# LightPlay1.net
KiCad netlist of a schematic drawn in EAGLE
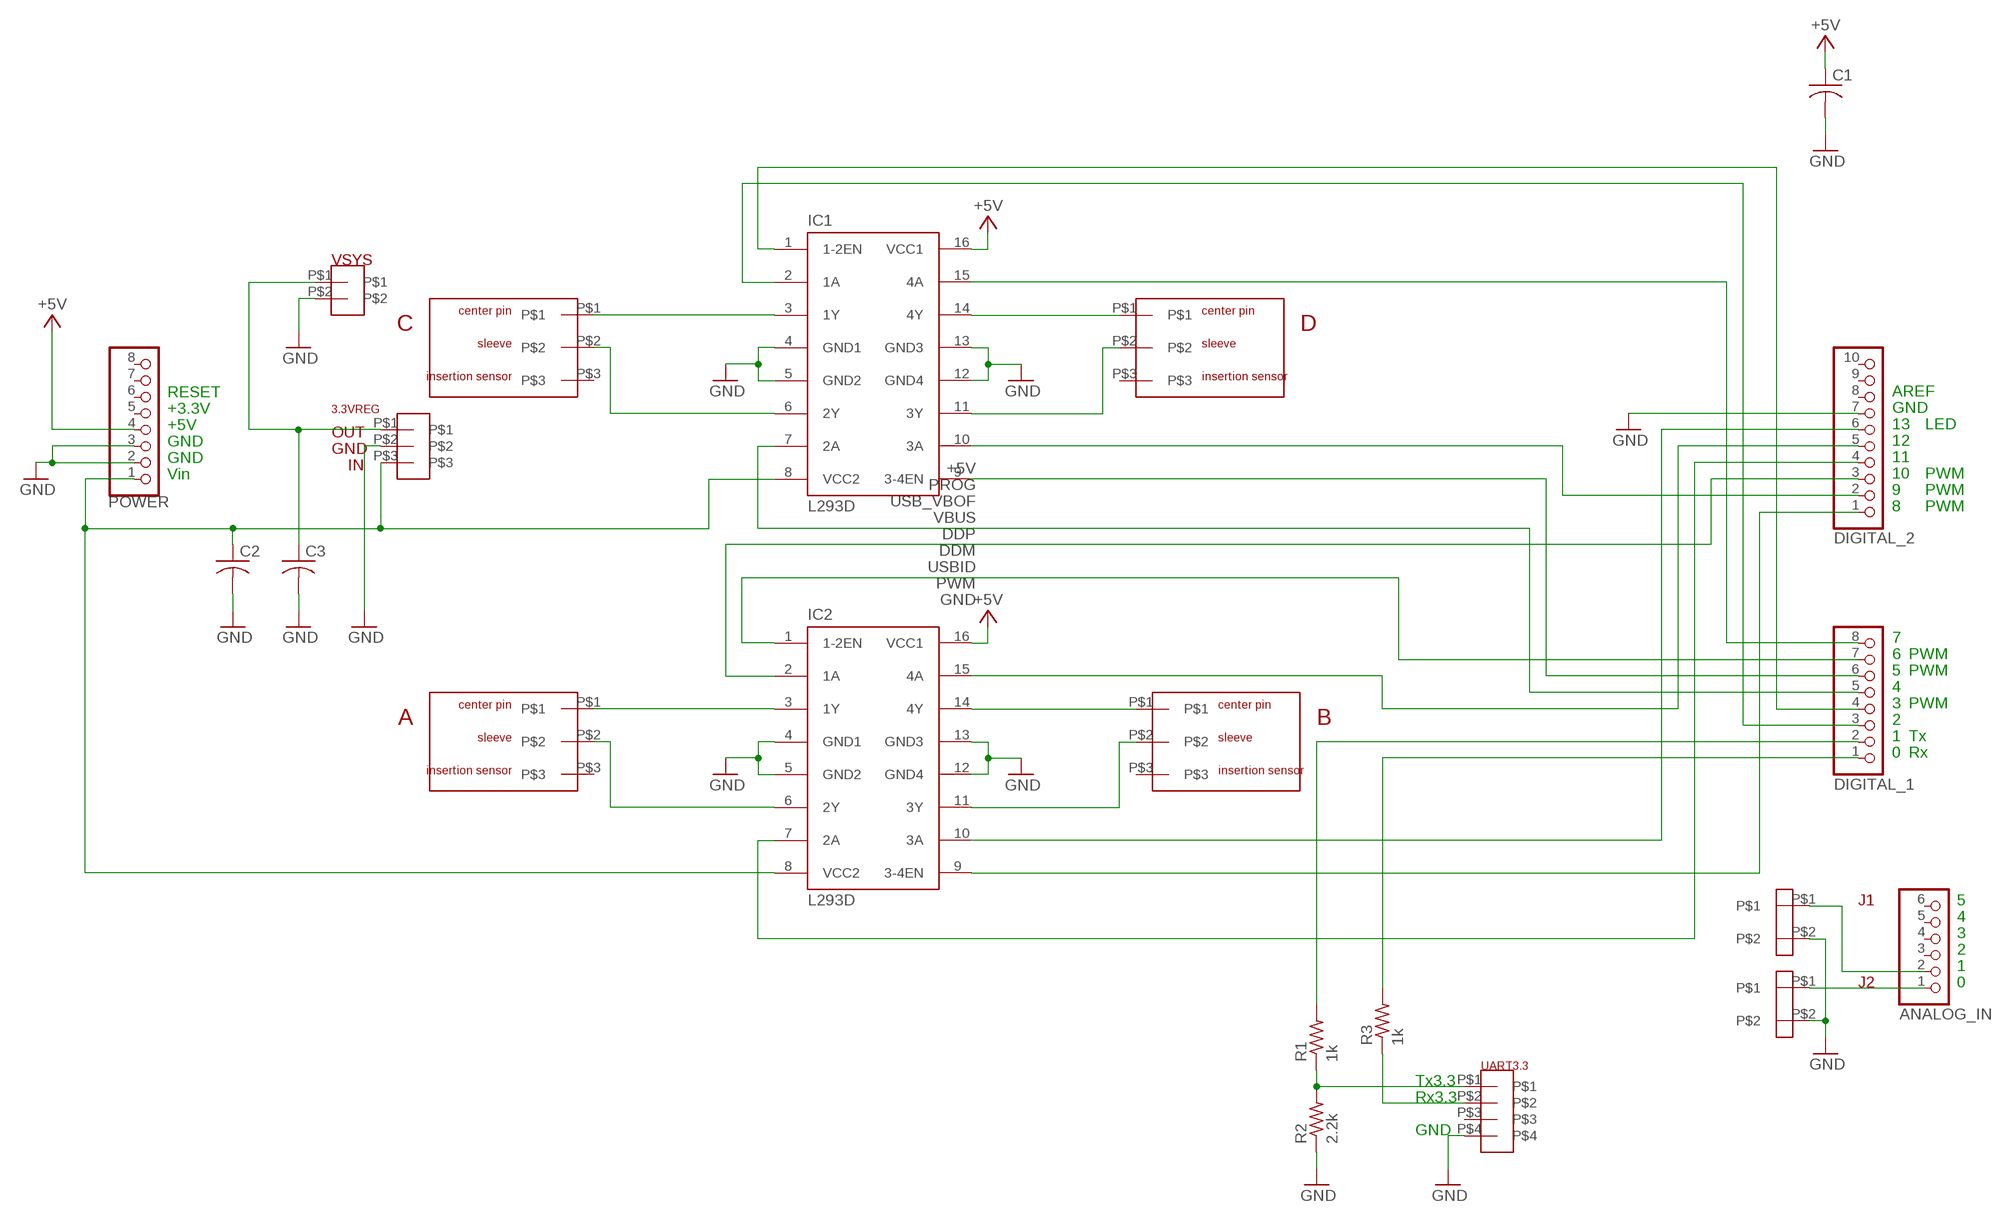
[diagram p0: schematic, sheet 1]

(export (version "E")
  (design (tool "Eeschema 10.0.6"))
  (components
    (comp (ref "3.3VREG")
      (value "LP38691_33REG")
      (footprint "eagle-import:TO-252")
      (libsource (lib "eagle-import") (part "LP38691_33REG"))
    )
    (comp (ref "A")
      (value "PJ-075DH-SMT-TR")
      (footprint "eagle-import:PJ-075DH-SMT-TR")
      (libsource (lib "eagle-import") (part "PJ-075DH-SMT-TR"))
    )
    (comp (ref "ANALOG_IN")
      (value "PINHD-1X6TH")
      (footprint "eagle-import:1X06-TH")
      (libsource (lib "eagle-import") (part "PINHD-1X6TH"))
    )
    (comp (ref "B")
      (value "PJ-075DH-SMT-TR")
      (footprint "eagle-import:PJ-075DH-SMT-TR")
      (libsource (lib "eagle-import") (part "PJ-075DH-SMT-TR"))
    )
    (comp (ref "C")
      (value "PJ-075DH-SMT-TR")
      (footprint "eagle-import:PJ-075DH-SMT-TR")
      (libsource (lib "eagle-import") (part "PJ-075DH-SMT-TR"))
    )
    (comp (ref "C1")
      (value "C-USC1206")
      (footprint "eagle-import:C1206")
      (libsource (lib "eagle-import") (part "C-USC1206"))
    )
    (comp (ref "C2")
      (value "C-USC1206")
      (footprint "eagle-import:C1206")
      (libsource (lib "eagle-import") (part "C-USC1206"))
    )
    (comp (ref "C3")
      (value "C-USC1206")
      (footprint "eagle-import:C1206")
      (libsource (lib "eagle-import") (part "C-USC1206"))
    )
    (comp (ref "D")
      (value "PJ-075DH-SMT-TR")
      (footprint "eagle-import:PJ-075DH-SMT-TR")
      (libsource (lib "eagle-import") (part "PJ-075DH-SMT-TR"))
    )
    (comp (ref "DIGITAL_1")
      (value "PINHD-1X8TH")
      (footprint "eagle-import:1X08-TH")
      (libsource (lib "eagle-import") (part "PINHD-1X8TH"))
    )
    (comp (ref "DIGITAL_2")
      (value "PINHD-1X10TH")
      (footprint "eagle-import:1X10-TH")
      (libsource (lib "eagle-import") (part "PINHD-1X10TH"))
    )
    (comp (ref "IC1")
      (value "L293D")
      (footprint "eagle-import:DIL16")
      (libsource (lib "eagle-import") (part "L293D"))
    )
    (comp (ref "IC2")
      (value "L293D")
      (footprint "eagle-import:DIL16")
      (libsource (lib "eagle-import") (part "L293D"))
    )
    (comp (ref "J1")
      (value "3.5MM_2PIN_SCREWTERMINAL_SPARKFUN")
      (footprint "eagle-import:1X02_3.5_SCREWTERM")
      (libsource (lib "eagle-import") (part "3.5MM_2PIN_SCREWTERMINAL_SPARKFUN"))
    )
    (comp (ref "J2")
      (value "3.5MM_2PIN_SCREWTERMINAL_SPARKFUN")
      (footprint "eagle-import:1X02_3.5_SCREWTERM")
      (libsource (lib "eagle-import") (part "3.5MM_2PIN_SCREWTERMINAL_SPARKFUN"))
    )
    (comp (ref "POWER")
      (value "PINHD-1X8TH")
      (footprint "eagle-import:1X08-TH")
      (libsource (lib "eagle-import") (part "PINHD-1X8TH"))
    )
    (comp (ref "R1")
      (value "1k")
      (footprint "eagle-import:M1206")
      (libsource (lib "eagle-import") (part "R-US_M1206"))
    )
    (comp (ref "R2")
      (value "2.2k")
      (footprint "eagle-import:M1206")
      (libsource (lib "eagle-import") (part "R-US_M1206"))
    )
    (comp (ref "R3")
      (value "1k")
      (footprint "eagle-import:M1206")
      (libsource (lib "eagle-import") (part "R-US_M1206"))
    )
    (comp (ref "UART3.3")
      (value "4PADS_ROBBIE")
      (footprint "eagle-import:1X04_ROBBIE")
      (libsource (lib "eagle-import") (part "4PADS_ROBBIE"))
    )
    (comp (ref "VSYS")
      (value "1X2HEADER_ROBBIE")
      (footprint "eagle-import:1X2HEADER_ROBBIE")
      (libsource (lib "eagle-import") (part "1X2HEADER_ROBBIE"))
    )
  )
  (nets
    (net (code "1") (name "+5V") (class "Default")
      (node (ref "C1") (pin "1") (pinfunction "1_1") (pintype "passive"))
      (node (ref "IC1") (pin "16") (pinfunction "VCC1_16") (pintype "power_in"))
      (node (ref "IC2") (pin "16") (pinfunction "VCC1_16") (pintype "power_in"))
      (node (ref "POWER") (pin "4") (pinfunction "4_4") (pintype "passive"))
    )
    (net (code "2") (name "GND") (class "Default")
      (node (ref "3.3VREG") (pin "P$2") (pinfunction "P$2_P$2") (pintype "bidirectional"))
      (node (ref "C1") (pin "2") (pinfunction "2_2") (pintype "passive"))
      (node (ref "C2") (pin "2") (pinfunction "2_2") (pintype "passive"))
      (node (ref "C3") (pin "2") (pinfunction "2_2") (pintype "passive"))
      (node (ref "DIGITAL_2") (pin "7") (pinfunction "7_7") (pintype "passive"))
      (node (ref "IC1") (pin "12") (pinfunction "GND4_12") (pintype "power_in"))
      (node (ref "IC1") (pin "13") (pinfunction "GND3_13") (pintype "power_in"))
      (node (ref "IC1") (pin "4") (pinfunction "GND1_4") (pintype "power_in"))
      (node (ref "IC1") (pin "5") (pinfunction "GND2_5") (pintype "power_in"))
      (node (ref "IC2") (pin "12") (pinfunction "GND4_12") (pintype "power_in"))
      (node (ref "IC2") (pin "13") (pinfunction "GND3_13") (pintype "power_in"))
      (node (ref "IC2") (pin "4") (pinfunction "GND1_4") (pintype "power_in"))
      (node (ref "IC2") (pin "5") (pinfunction "GND2_5") (pintype "power_in"))
      (node (ref "J1") (pin "P$2") (pinfunction "P$2_P$2") (pintype "bidirectional"))
      (node (ref "J2") (pin "P$2") (pinfunction "P$2_P$2") (pintype "bidirectional"))
      (node (ref "POWER") (pin "2") (pinfunction "2_2") (pintype "passive"))
      (node (ref "POWER") (pin "3") (pinfunction "3_3") (pintype "passive"))
      (node (ref "R2") (pin "1") (pinfunction "1_1") (pintype "passive"))
      (node (ref "UART3.3") (pin "P$4") (pinfunction "P$4_P$4") (pintype "bidirectional"))
      (node (ref "VSYS") (pin "P$2") (pinfunction "P$2_P$2") (pintype "bidirectional"))
    )
    (net (code "3") (name "Net-(3.3VREG-PadP$1)") (class "Default")
      (node (ref "3.3VREG") (pin "P$1") (pinfunction "P$1_P$1") (pintype "bidirectional"))
      (node (ref "C3") (pin "1") (pinfunction "1_1") (pintype "passive"))
      (node (ref "VSYS") (pin "P$1") (pinfunction "P$1_P$1") (pintype "bidirectional"))
    )
    (net (code "4") (name "Net-(ANALOG_IN-Pad1)") (class "Default")
      (node (ref "ANALOG_IN") (pin "1") (pinfunction "1_1") (pintype "passive"))
      (node (ref "J2") (pin "P$1") (pinfunction "P$1_P$1") (pintype "bidirectional"))
    )
    (net (code "5") (name "Net-(ANALOG_IN-Pad2)") (class "Default")
      (node (ref "ANALOG_IN") (pin "2") (pinfunction "2_2") (pintype "passive"))
      (node (ref "J1") (pin "P$1") (pinfunction "P$1_P$1") (pintype "bidirectional"))
    )
    (net (code "6") (name "Net-(DIGITAL_1-Pad1)") (class "Default")
      (node (ref "DIGITAL_1") (pin "1") (pinfunction "1_1") (pintype "passive"))
      (node (ref "R3") (pin "2") (pinfunction "2_2") (pintype "passive"))
    )
    (net (code "7") (name "Net-(DIGITAL_1-Pad2)") (class "Default")
      (node (ref "DIGITAL_1") (pin "2") (pinfunction "2_2") (pintype "passive"))
      (node (ref "R1") (pin "2") (pinfunction "2_2") (pintype "passive"))
    )
    (net (code "8") (name "Net-(IC1-1-2EN)") (class "Default")
      (node (ref "DIGITAL_1") (pin "4") (pinfunction "4_4") (pintype "passive"))
      (node (ref "IC1") (pin "1") (pinfunction "1-2EN_1") (pintype "input"))
    )
    (net (code "9") (name "Net-(IC1-1A)") (class "Default")
      (node (ref "DIGITAL_1") (pin "3") (pinfunction "3_3") (pintype "passive"))
      (node (ref "IC1") (pin "2") (pinfunction "1A_2") (pintype "input"))
    )
    (net (code "10") (name "Net-(IC1-1Y)") (class "Default")
      (node (ref "C") (pin "P$1") (pinfunction "P$1_P$1") (pintype "bidirectional"))
      (node (ref "IC1") (pin "3") (pinfunction "1Y_3") (pintype "output"))
    )
    (net (code "11") (name "Net-(IC1-2A)") (class "Default")
      (node (ref "DIGITAL_1") (pin "5") (pinfunction "5_5") (pintype "passive"))
      (node (ref "IC1") (pin "7") (pinfunction "2A_7") (pintype "input"))
    )
    (net (code "12") (name "Net-(IC1-2Y)") (class "Default")
      (node (ref "C") (pin "P$2") (pinfunction "P$2_P$2") (pintype "bidirectional"))
      (node (ref "IC1") (pin "6") (pinfunction "2Y_6") (pintype "output"))
    )
    (net (code "13") (name "Net-(IC1-3-4EN)") (class "Default")
      (node (ref "DIGITAL_1") (pin "6") (pinfunction "6_6") (pintype "passive"))
      (node (ref "IC1") (pin "9") (pinfunction "3-4EN_9") (pintype "input"))
    )
    (net (code "14") (name "Net-(IC1-3A)") (class "Default")
      (node (ref "DIGITAL_2") (pin "2") (pinfunction "2_2") (pintype "passive"))
      (node (ref "IC1") (pin "10") (pinfunction "3A_10") (pintype "input"))
    )
    (net (code "15") (name "Net-(IC1-3Y)") (class "Default")
      (node (ref "D") (pin "P$2") (pinfunction "P$2_P$2") (pintype "bidirectional"))
      (node (ref "IC1") (pin "11") (pinfunction "3Y_11") (pintype "output"))
    )
    (net (code "16") (name "Net-(IC1-4A)") (class "Default")
      (node (ref "DIGITAL_1") (pin "8") (pinfunction "8_8") (pintype "passive"))
      (node (ref "IC1") (pin "15") (pinfunction "4A_15") (pintype "input"))
    )
    (net (code "17") (name "Net-(IC1-4Y)") (class "Default")
      (node (ref "D") (pin "P$1") (pinfunction "P$1_P$1") (pintype "bidirectional"))
      (node (ref "IC1") (pin "14") (pinfunction "4Y_14") (pintype "output"))
    )
    (net (code "18") (name "Net-(IC1-VCC2)") (class "Default")
      (node (ref "3.3VREG") (pin "P$3") (pinfunction "P$3_P$3") (pintype "bidirectional"))
      (node (ref "C2") (pin "1") (pinfunction "1_1") (pintype "passive"))
      (node (ref "IC1") (pin "8") (pinfunction "VCC2_8") (pintype "power_in"))
      (node (ref "IC2") (pin "8") (pinfunction "VCC2_8") (pintype "power_in"))
      (node (ref "POWER") (pin "1") (pinfunction "1_1") (pintype "passive"))
    )
    (net (code "19") (name "Net-(IC2-1-2EN)") (class "Default")
      (node (ref "DIGITAL_1") (pin "7") (pinfunction "7_7") (pintype "passive"))
      (node (ref "IC2") (pin "1") (pinfunction "1-2EN_1") (pintype "input"))
    )
    (net (code "20") (name "Net-(IC2-1A)") (class "Default")
      (node (ref "DIGITAL_2") (pin "3") (pinfunction "3_3") (pintype "passive"))
      (node (ref "IC2") (pin "2") (pinfunction "1A_2") (pintype "input"))
    )
    (net (code "21") (name "Net-(IC2-1Y)") (class "Default")
      (node (ref "A") (pin "P$1") (pinfunction "P$1_P$1") (pintype "bidirectional"))
      (node (ref "IC2") (pin "3") (pinfunction "1Y_3") (pintype "output"))
    )
    (net (code "22") (name "Net-(IC2-2A)") (class "Default")
      (node (ref "DIGITAL_2") (pin "4") (pinfunction "4_4") (pintype "passive"))
      (node (ref "IC2") (pin "7") (pinfunction "2A_7") (pintype "input"))
    )
    (net (code "23") (name "Net-(IC2-2Y)") (class "Default")
      (node (ref "A") (pin "P$2") (pinfunction "P$2_P$2") (pintype "bidirectional"))
      (node (ref "IC2") (pin "6") (pinfunction "2Y_6") (pintype "output"))
    )
    (net (code "24") (name "Net-(IC2-3-4EN)") (class "Default")
      (node (ref "DIGITAL_2") (pin "1") (pinfunction "1_1") (pintype "passive"))
      (node (ref "IC2") (pin "9") (pinfunction "3-4EN_9") (pintype "input"))
    )
    (net (code "25") (name "Net-(IC2-3A)") (class "Default")
      (node (ref "DIGITAL_2") (pin "6") (pinfunction "6_6") (pintype "passive"))
      (node (ref "IC2") (pin "10") (pinfunction "3A_10") (pintype "input"))
    )
    (net (code "26") (name "Net-(IC2-3Y)") (class "Default")
      (node (ref "B") (pin "P$2") (pinfunction "P$2_P$2") (pintype "bidirectional"))
      (node (ref "IC2") (pin "11") (pinfunction "3Y_11") (pintype "output"))
    )
    (net (code "27") (name "Net-(IC2-4A)") (class "Default")
      (node (ref "DIGITAL_2") (pin "5") (pinfunction "5_5") (pintype "passive"))
      (node (ref "IC2") (pin "15") (pinfunction "4A_15") (pintype "input"))
    )
    (net (code "28") (name "Net-(IC2-4Y)") (class "Default")
      (node (ref "B") (pin "P$1") (pinfunction "P$1_P$1") (pintype "bidirectional"))
      (node (ref "IC2") (pin "14") (pinfunction "4Y_14") (pintype "output"))
    )
    (net (code "29") (name "Net-(R1-Pad1)") (class "Default")
      (node (ref "R1") (pin "1") (pinfunction "1_1") (pintype "passive"))
      (node (ref "R2") (pin "2") (pinfunction "2_2") (pintype "passive"))
      (node (ref "UART3.3") (pin "P$1") (pinfunction "P$1_P$1") (pintype "bidirectional"))
    )
    (net (code "30") (name "Net-(R3-Pad1)") (class "Default")
      (node (ref "R3") (pin "1") (pinfunction "1_1") (pintype "passive"))
      (node (ref "UART3.3") (pin "P$2") (pinfunction "P$2_P$2") (pintype "bidirectional"))
    )
    (net (code "31") (name "unconnected-(A-PadP$3)") (class "Default")
      (node (ref "A") (pin "P$3") (pinfunction "P$3_P$3") (pintype "bidirectional"))
    )
    (net (code "32") (name "unconnected-(ANALOG_IN-Pad3)") (class "Default")
      (node (ref "ANALOG_IN") (pin "3") (pinfunction "3_3") (pintype "passive"))
    )
    (net (code "33") (name "unconnected-(ANALOG_IN-Pad4)") (class "Default")
      (node (ref "ANALOG_IN") (pin "4") (pinfunction "4_4") (pintype "passive"))
    )
    (net (code "34") (name "unconnected-(ANALOG_IN-Pad5)") (class "Default")
      (node (ref "ANALOG_IN") (pin "5") (pinfunction "5_5") (pintype "passive"))
    )
    (net (code "35") (name "unconnected-(ANALOG_IN-Pad6)") (class "Default")
      (node (ref "ANALOG_IN") (pin "6") (pinfunction "6_6") (pintype "passive"))
    )
    (net (code "36") (name "unconnected-(B-PadP$3)") (class "Default")
      (node (ref "B") (pin "P$3") (pinfunction "P$3_P$3") (pintype "bidirectional"))
    )
    (net (code "37") (name "unconnected-(C-PadP$3)") (class "Default")
      (node (ref "C") (pin "P$3") (pinfunction "P$3_P$3") (pintype "bidirectional"))
    )
    (net (code "38") (name "unconnected-(D-PadP$3)") (class "Default")
      (node (ref "D") (pin "P$3") (pinfunction "P$3_P$3") (pintype "bidirectional"))
    )
    (net (code "39") (name "unconnected-(DIGITAL_2-Pad8)") (class "Default")
      (node (ref "DIGITAL_2") (pin "8") (pinfunction "8_8") (pintype "passive"))
    )
    (net (code "40") (name "unconnected-(DIGITAL_2-Pad9)") (class "Default")
      (node (ref "DIGITAL_2") (pin "9") (pinfunction "9_9") (pintype "passive"))
    )
    (net (code "41") (name "unconnected-(DIGITAL_2-Pad10)") (class "Default")
      (node (ref "DIGITAL_2") (pin "10") (pinfunction "10_10") (pintype "passive"))
    )
    (net (code "42") (name "unconnected-(POWER-Pad5)") (class "Default")
      (node (ref "POWER") (pin "5") (pinfunction "5_5") (pintype "passive"))
    )
    (net (code "43") (name "unconnected-(POWER-Pad6)") (class "Default")
      (node (ref "POWER") (pin "6") (pinfunction "6_6") (pintype "passive"))
    )
    (net (code "44") (name "unconnected-(POWER-Pad7)") (class "Default")
      (node (ref "POWER") (pin "7") (pinfunction "7_7") (pintype "passive"))
    )
    (net (code "45") (name "unconnected-(POWER-Pad8)") (class "Default")
      (node (ref "POWER") (pin "8") (pinfunction "8_8") (pintype "passive"))
    )
    (net (code "46") (name "unconnected-(UART3.3-PadP$3)") (class "Default")
      (node (ref "UART3.3") (pin "P$3") (pinfunction "P$3_P$3") (pintype "bidirectional"))
    )
  )
)
